# I2C.net
KiCad netlist of a schematic drawn in EAGLE
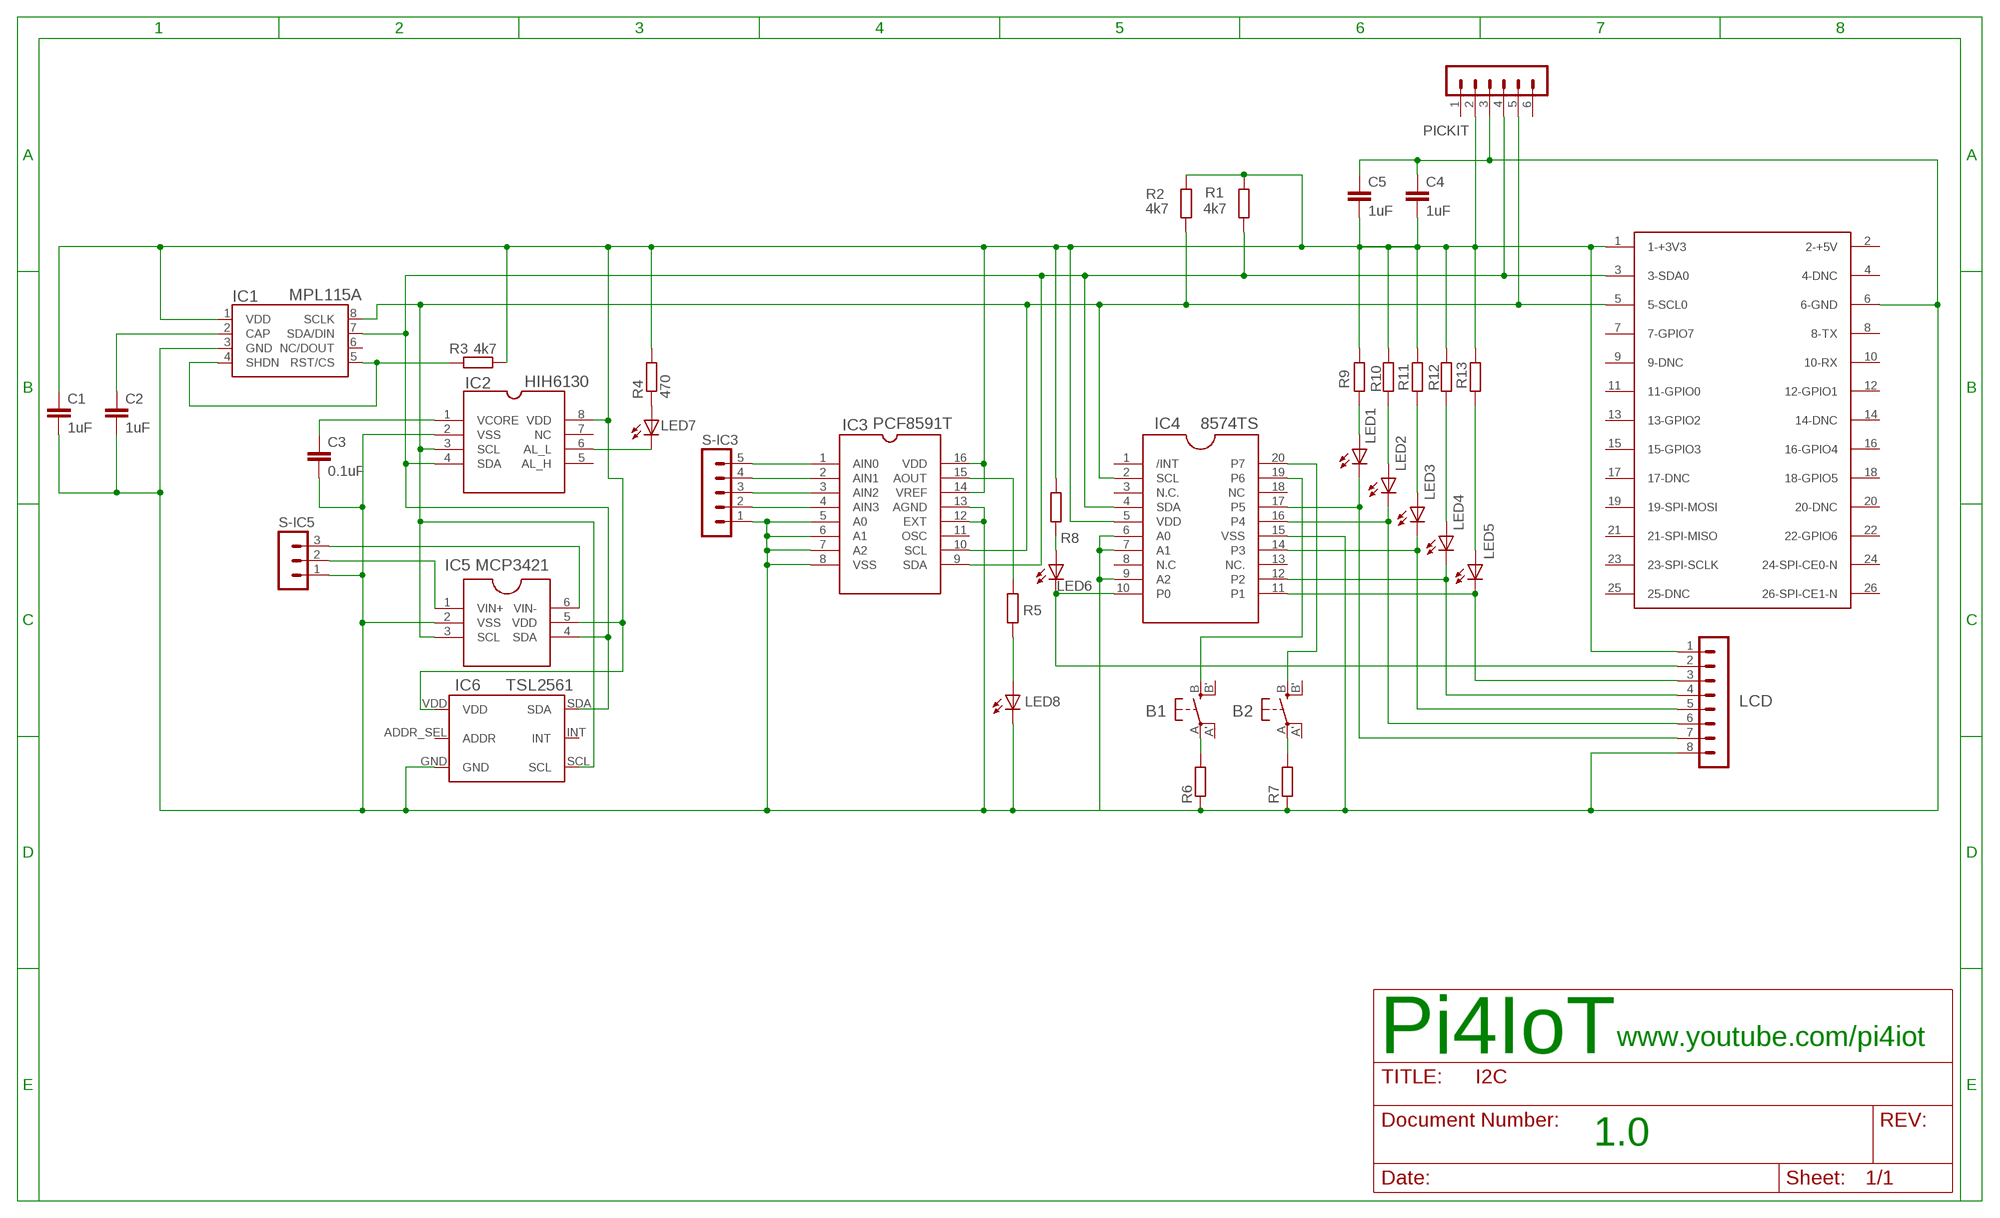
[diagram p0: schematic, sheet 1]

(export (version "E")
  (design (tool "Eeschema 10.0.6"))
  (components
    (comp (ref "B1")
      (value "SWITCH_TACT_SMT")
      (footprint "eagle-import:EVQ-Q2")
      (libsource (lib "eagle-import") (part "SWITCH_TACT_SMT"))
    )
    (comp (ref "B2")
      (value "SWITCH_TACT_SMT")
      (footprint "eagle-import:EVQ-Q2")
      (libsource (lib "eagle-import") (part "SWITCH_TACT_SMT"))
    )
    (comp (ref "C1")
      (value "1uF")
      (footprint "eagle-import:C1206")
      (libsource (lib "eagle-import") (part "C-EUC1206"))
    )
    (comp (ref "C2")
      (value "1uF")
      (footprint "eagle-import:C1206")
      (libsource (lib "eagle-import") (part "C-EUC1206"))
    )
    (comp (ref "C3")
      (value "0.1uF")
      (footprint "eagle-import:C1206")
      (libsource (lib "eagle-import") (part "C-EUC1206"))
    )
    (comp (ref "C4")
      (value "1uF")
      (footprint "eagle-import:C1206")
      (libsource (lib "eagle-import") (part "C-EUC1206"))
    )
    (comp (ref "C5")
      (value "1uF")
      (footprint "eagle-import:C1206")
      (libsource (lib "eagle-import") (part "C-EUC1206"))
    )
    (comp (ref "IC1")
      (value "MPL115A")
      (footprint "eagle-import:LGA8")
      (libsource (lib "eagle-import") (part "MPL115A"))
    )
    (comp (ref "IC2")
      (value "HIH6130")
      (footprint "eagle-import:SO08")
      (libsource (lib "eagle-import") (part "HIH6130"))
    )
    (comp (ref "IC3")
      (value "PCF8591T")
      (footprint "eagle-import:SO-16W")
      (libsource (lib "eagle-import") (part "PCF8591T"))
    )
    (comp (ref "IC4")
      (value "8574TS")
      (footprint "eagle-import:SSOP20")
      (libsource (lib "eagle-import") (part "8574TS"))
    )
    (comp (ref "IC5")
      (value "MCP3421")
      (footprint "eagle-import:SOT23-6")
      (libsource (lib "eagle-import") (part "MCP3421A0T"))
    )
    (comp (ref "IC6")
      (value "TSL2561")
      (footprint "eagle-import:TSL2561T")
      (libsource (lib "eagle-import") (part "TSL2561T"))
    )
    (comp (ref "LCD")
      (value "MA08-1")
      (footprint "eagle-import:MA08-1")
      (libsource (lib "eagle-import") (part "MA08-1"))
    )
    (comp (ref "LED1")
      (value "LEDSML0603")
      (footprint "eagle-import:SML0603")
      (libsource (lib "eagle-import") (part "LEDSML0603"))
    )
    (comp (ref "LED2")
      (value "LEDSML0603")
      (footprint "eagle-import:SML0603")
      (libsource (lib "eagle-import") (part "LEDSML0603"))
    )
    (comp (ref "LED3")
      (value "LEDSML0603")
      (footprint "eagle-import:SML0603")
      (libsource (lib "eagle-import") (part "LEDSML0603"))
    )
    (comp (ref "LED4")
      (value "LEDSML0603")
      (footprint "eagle-import:SML0603")
      (libsource (lib "eagle-import") (part "LEDSML0603"))
    )
    (comp (ref "LED5")
      (value "LEDSML0603")
      (footprint "eagle-import:SML0603")
      (libsource (lib "eagle-import") (part "LEDSML0603"))
    )
    (comp (ref "LED6")
      (value "LEDSML0603")
      (footprint "eagle-import:SML0603")
      (libsource (lib "eagle-import") (part "LEDSML0603"))
    )
    (comp (ref "LED7")
      (value "LEDSML0603")
      (footprint "eagle-import:SML0603")
      (libsource (lib "eagle-import") (part "LEDSML0603"))
    )
    (comp (ref "LED8")
      (value "LEDSML0603")
      (footprint "eagle-import:SML0603")
      (libsource (lib "eagle-import") (part "LEDSML0603"))
    )
    (comp (ref "PI")
      (value "RASPBERRY-PI")
      (footprint "eagle-import:RASPBERRY-PI")
      (libsource (lib "eagle-import") (part "RASPBERRY-PI"))
    )
    (comp (ref "PICKIT")
      (value "MA06-1")
      (footprint "eagle-import:MA06-1")
      (libsource (lib "eagle-import") (part "MA06-1"))
    )
    (comp (ref "R1")
      (value "4k7")
      (footprint "eagle-import:R0603")
      (libsource (lib "eagle-import") (part "R-EU_R0603"))
    )
    (comp (ref "R2")
      (value "4k7")
      (footprint "eagle-import:R0603")
      (libsource (lib "eagle-import") (part "R-EU_R0603"))
    )
    (comp (ref "R3")
      (value "4k7")
      (footprint "eagle-import:R0603")
      (libsource (lib "eagle-import") (part "R-EU_R0603"))
    )
    (comp (ref "R4")
      (value "470")
      (footprint "eagle-import:R0603")
      (libsource (lib "eagle-import") (part "R-EU_R0603"))
    )
    (comp (ref "R5")
      (value "R-EU_R0603")
      (footprint "eagle-import:R0603")
      (libsource (lib "eagle-import") (part "R-EU_R0603"))
    )
    (comp (ref "R6")
      (value "R-EU_R0603")
      (footprint "eagle-import:R0603")
      (libsource (lib "eagle-import") (part "R-EU_R0603"))
    )
    (comp (ref "R7")
      (value "R-EU_R0603")
      (footprint "eagle-import:R0603")
      (libsource (lib "eagle-import") (part "R-EU_R0603"))
    )
    (comp (ref "R8")
      (value "R-EU_R0603")
      (footprint "eagle-import:R0603")
      (libsource (lib "eagle-import") (part "R-EU_R0603"))
    )
    (comp (ref "R9")
      (value "R-EU_R0603")
      (footprint "eagle-import:R0603")
      (libsource (lib "eagle-import") (part "R-EU_R0603"))
    )
    (comp (ref "R10")
      (value "R-EU_R0603")
      (footprint "eagle-import:R0603")
      (libsource (lib "eagle-import") (part "R-EU_R0603"))
    )
    (comp (ref "R11")
      (value "R-EU_R0603")
      (footprint "eagle-import:R0603")
      (libsource (lib "eagle-import") (part "R-EU_R0603"))
    )
    (comp (ref "R12")
      (value "R-EU_R0603")
      (footprint "eagle-import:R0603")
      (libsource (lib "eagle-import") (part "R-EU_R0603"))
    )
    (comp (ref "R13")
      (value "R-EU_R0603")
      (footprint "eagle-import:R0603")
      (libsource (lib "eagle-import") (part "R-EU_R0603"))
    )
    (comp (ref "S-IC3")
      (value "MA05-1")
      (footprint "eagle-import:MA05-1")
      (libsource (lib "eagle-import") (part "MA05-1"))
    )
    (comp (ref "S-IC5")
      (value "MA03-1")
      (footprint "eagle-import:MA03-1")
      (libsource (lib "eagle-import") (part "MA03-1"))
    )
  )
  (nets
    (net (code "1") (name "Net-(B1-P)") (class "Default")
      (node (ref "B1") (pin "A") (pinfunction "P_A") (pintype "passive"))
      (node (ref "R6") (pin "2") (pinfunction "2_2") (pintype "passive"))
    )
    (net (code "2") (name "Net-(B1-S)") (class "Default")
      (node (ref "B1") (pin "B") (pinfunction "S_B") (pintype "passive"))
      (node (ref "IC4") (pin "19") (pinfunction "P6_19") (pintype "bidirectional"))
    )
    (net (code "3") (name "Net-(B2-P)") (class "Default")
      (node (ref "B2") (pin "A") (pinfunction "P_A") (pintype "passive"))
      (node (ref "R7") (pin "2") (pinfunction "2_2") (pintype "passive"))
    )
    (net (code "4") (name "Net-(B2-S)") (class "Default")
      (node (ref "B2") (pin "B") (pinfunction "S_B") (pintype "passive"))
      (node (ref "IC4") (pin "20") (pinfunction "P7_20") (pintype "bidirectional"))
    )
    (net (code "5") (name "Net-(IC1-CAP)") (class "Default")
      (node (ref "C2") (pin "1") (pinfunction "1_1") (pintype "passive"))
      (node (ref "IC1") (pin "2") (pinfunction "CAP_2") (pintype "bidirectional"))
    )
    (net (code "6") (name "Net-(IC1-GND)") (class "Default")
      (node (ref "C1") (pin "2") (pinfunction "2_2") (pintype "passive"))
      (node (ref "C2") (pin "2") (pinfunction "2_2") (pintype "passive"))
      (node (ref "C3") (pin "2") (pinfunction "2_2") (pintype "passive"))
      (node (ref "C4") (pin "1") (pinfunction "1_1") (pintype "passive"))
      (node (ref "C5") (pin "1") (pinfunction "1_1") (pintype "passive"))
      (node (ref "IC1") (pin "3") (pinfunction "GND_3") (pintype "bidirectional"))
      (node (ref "IC2") (pin "2") (pinfunction "VSS_2") (pintype "bidirectional"))
      (node (ref "IC3") (pin "12") (pinfunction "EXT_12") (pintype "bidirectional"))
      (node (ref "IC3") (pin "13") (pinfunction "AGND_13") (pintype "bidirectional"))
      (node (ref "IC3") (pin "5") (pinfunction "A0_5") (pintype "bidirectional"))
      (node (ref "IC3") (pin "6") (pinfunction "A1_6") (pintype "bidirectional"))
      (node (ref "IC3") (pin "7") (pinfunction "A2_7") (pintype "bidirectional"))
      (node (ref "IC3") (pin "8") (pinfunction "VSS_8") (pintype "bidirectional"))
      (node (ref "IC4") (pin "15") (pinfunction "VSS_15") (pintype "bidirectional"))
      (node (ref "IC4") (pin "6") (pinfunction "A0_6") (pintype "bidirectional"))
      (node (ref "IC4") (pin "7") (pinfunction "A1_7") (pintype "bidirectional"))
      (node (ref "IC4") (pin "9") (pinfunction "A2_9") (pintype "bidirectional"))
      (node (ref "IC5") (pin "2") (pinfunction "VSS_2") (pintype "bidirectional"))
      (node (ref "IC6") (pin "GND") (pinfunction "GND_GND") (pintype "passive"))
      (node (ref "LCD") (pin "8") (pinfunction "8_8") (pintype "passive"))
      (node (ref "LED8") (pin "C") (pinfunction "C_C") (pintype "passive"))
      (node (ref "PI") (pin "6") (pinfunction "6-GND_6") (pintype "bidirectional"))
      (node (ref "PICKIT") (pin "3") (pinfunction "3_3") (pintype "passive"))
      (node (ref "R6") (pin "1") (pinfunction "1_1") (pintype "passive"))
      (node (ref "R7") (pin "1") (pinfunction "1_1") (pintype "passive"))
      (node (ref "S-IC3") (pin "1") (pinfunction "1_1") (pintype "passive"))
      (node (ref "S-IC5") (pin "1") (pinfunction "1_1") (pintype "passive"))
    )
    (net (code "7") (name "Net-(IC1-RST{slash}CS)") (class "Default")
      (node (ref "IC1") (pin "4") (pinfunction "SHDN_4") (pintype "bidirectional"))
      (node (ref "IC1") (pin "5") (pinfunction "RST/CS_5") (pintype "bidirectional"))
      (node (ref "R3") (pin "2") (pinfunction "2_2") (pintype "passive"))
    )
    (net (code "8") (name "Net-(IC1-SCLK)") (class "Default")
      (node (ref "IC1") (pin "8") (pinfunction "SCLK_8") (pintype "bidirectional"))
      (node (ref "IC2") (pin "3") (pinfunction "SCL_3") (pintype "bidirectional"))
      (node (ref "IC3") (pin "10") (pinfunction "SCL_10") (pintype "bidirectional"))
      (node (ref "IC4") (pin "2") (pinfunction "SCL_2") (pintype "bidirectional"))
      (node (ref "IC5") (pin "3") (pinfunction "SCL_3") (pintype "bidirectional"))
      (node (ref "IC6") (pin "SCL") (pinfunction "SCL_SCL") (pintype "passive"))
      (node (ref "PI") (pin "5") (pinfunction "5-SCL0_5") (pintype "bidirectional"))
      (node (ref "PICKIT") (pin "5") (pinfunction "5_5") (pintype "passive"))
      (node (ref "R2") (pin "1") (pinfunction "1_1") (pintype "passive"))
    )
    (net (code "9") (name "Net-(IC1-SDA{slash}DIN)") (class "Default")
      (node (ref "IC1") (pin "7") (pinfunction "SDA/DIN_7") (pintype "bidirectional"))
      (node (ref "IC2") (pin "4") (pinfunction "SDA_4") (pintype "bidirectional"))
      (node (ref "IC3") (pin "9") (pinfunction "SDA_9") (pintype "bidirectional"))
      (node (ref "IC4") (pin "4") (pinfunction "SDA_4") (pintype "bidirectional"))
      (node (ref "IC5") (pin "4") (pinfunction "SDA_4") (pintype "bidirectional"))
      (node (ref "IC6") (pin "SDA") (pinfunction "SDA_SDA") (pintype "passive"))
      (node (ref "PI") (pin "3") (pinfunction "3-SDA0_3") (pintype "bidirectional"))
      (node (ref "PICKIT") (pin "4") (pinfunction "4_4") (pintype "passive"))
      (node (ref "R1") (pin "1") (pinfunction "1_1") (pintype "passive"))
    )
    (net (code "10") (name "Net-(IC1-VDD)") (class "Default")
      (node (ref "C1") (pin "1") (pinfunction "1_1") (pintype "passive"))
      (node (ref "C4") (pin "2") (pinfunction "2_2") (pintype "passive"))
      (node (ref "C5") (pin "2") (pinfunction "2_2") (pintype "passive"))
      (node (ref "IC1") (pin "1") (pinfunction "VDD_1") (pintype "bidirectional"))
      (node (ref "IC2") (pin "8") (pinfunction "VDD_8") (pintype "bidirectional"))
      (node (ref "IC3") (pin "14") (pinfunction "VREF_14") (pintype "bidirectional"))
      (node (ref "IC3") (pin "16") (pinfunction "VDD_16") (pintype "bidirectional"))
      (node (ref "IC4") (pin "5") (pinfunction "VDD_5") (pintype "bidirectional"))
      (node (ref "IC5") (pin "5") (pinfunction "VDD_5") (pintype "bidirectional"))
      (node (ref "IC6") (pin "VDD") (pinfunction "VDD_VDD") (pintype "passive"))
      (node (ref "LCD") (pin "1") (pinfunction "1_1") (pintype "passive"))
      (node (ref "PI") (pin "1") (pinfunction "1-+3V3_1") (pintype "bidirectional"))
      (node (ref "PICKIT") (pin "2") (pinfunction "2_2") (pintype "passive"))
      (node (ref "R1") (pin "2") (pinfunction "2_2") (pintype "passive"))
      (node (ref "R10") (pin "2") (pinfunction "2_2") (pintype "passive"))
      (node (ref "R11") (pin "2") (pinfunction "2_2") (pintype "passive"))
      (node (ref "R12") (pin "2") (pinfunction "2_2") (pintype "passive"))
      (node (ref "R13") (pin "2") (pinfunction "2_2") (pintype "passive"))
      (node (ref "R2") (pin "2") (pinfunction "2_2") (pintype "passive"))
      (node (ref "R3") (pin "1") (pinfunction "1_1") (pintype "passive"))
      (node (ref "R4") (pin "2") (pinfunction "2_2") (pintype "passive"))
      (node (ref "R8") (pin "2") (pinfunction "2_2") (pintype "passive"))
      (node (ref "R9") (pin "2") (pinfunction "2_2") (pintype "passive"))
    )
    (net (code "11") (name "Net-(IC2-AL_L)") (class "Default")
      (node (ref "IC2") (pin "6") (pinfunction "AL_L_6") (pintype "bidirectional"))
      (node (ref "LED7") (pin "C") (pinfunction "C_C") (pintype "passive"))
    )
    (net (code "12") (name "Net-(IC2-VCORE)") (class "Default")
      (node (ref "C3") (pin "1") (pinfunction "1_1") (pintype "passive"))
      (node (ref "IC2") (pin "1") (pinfunction "VCORE_1") (pintype "bidirectional"))
    )
    (net (code "13") (name "Net-(IC3-AIN0)") (class "Default")
      (node (ref "IC3") (pin "1") (pinfunction "AIN0_1") (pintype "bidirectional"))
      (node (ref "S-IC3") (pin "5") (pinfunction "5_5") (pintype "passive"))
    )
    (net (code "14") (name "Net-(IC3-AIN1)") (class "Default")
      (node (ref "IC3") (pin "2") (pinfunction "AIN1_2") (pintype "bidirectional"))
      (node (ref "S-IC3") (pin "4") (pinfunction "4_4") (pintype "passive"))
    )
    (net (code "15") (name "Net-(IC3-AIN2)") (class "Default")
      (node (ref "IC3") (pin "3") (pinfunction "AIN2_3") (pintype "bidirectional"))
      (node (ref "S-IC3") (pin "3") (pinfunction "3_3") (pintype "passive"))
    )
    (net (code "16") (name "Net-(IC3-AIN3)") (class "Default")
      (node (ref "IC3") (pin "4") (pinfunction "AIN3_4") (pintype "bidirectional"))
      (node (ref "S-IC3") (pin "2") (pinfunction "2_2") (pintype "passive"))
    )
    (net (code "17") (name "Net-(IC3-AOUT)") (class "Default")
      (node (ref "IC3") (pin "15") (pinfunction "AOUT_15") (pintype "bidirectional"))
      (node (ref "R5") (pin "2") (pinfunction "2_2") (pintype "passive"))
    )
    (net (code "18") (name "Net-(IC4-P0)") (class "Default")
      (node (ref "IC4") (pin "10") (pinfunction "P0_10") (pintype "bidirectional"))
      (node (ref "LCD") (pin "2") (pinfunction "2_2") (pintype "passive"))
      (node (ref "LED6") (pin "C") (pinfunction "C_C") (pintype "passive"))
    )
    (net (code "19") (name "Net-(IC4-P1)") (class "Default")
      (node (ref "IC4") (pin "11") (pinfunction "P1_11") (pintype "bidirectional"))
      (node (ref "LCD") (pin "3") (pinfunction "3_3") (pintype "passive"))
      (node (ref "LED5") (pin "C") (pinfunction "C_C") (pintype "passive"))
    )
    (net (code "20") (name "Net-(IC4-P2)") (class "Default")
      (node (ref "IC4") (pin "12") (pinfunction "P2_12") (pintype "bidirectional"))
      (node (ref "LCD") (pin "4") (pinfunction "4_4") (pintype "passive"))
      (node (ref "LED4") (pin "C") (pinfunction "C_C") (pintype "passive"))
    )
    (net (code "21") (name "Net-(IC4-P3)") (class "Default")
      (node (ref "IC4") (pin "14") (pinfunction "P3_14") (pintype "bidirectional"))
      (node (ref "LCD") (pin "5") (pinfunction "5_5") (pintype "passive"))
      (node (ref "LED3") (pin "C") (pinfunction "C_C") (pintype "passive"))
    )
    (net (code "22") (name "Net-(IC4-P4)") (class "Default")
      (node (ref "IC4") (pin "16") (pinfunction "P4_16") (pintype "bidirectional"))
      (node (ref "LCD") (pin "6") (pinfunction "6_6") (pintype "passive"))
      (node (ref "LED2") (pin "C") (pinfunction "C_C") (pintype "passive"))
    )
    (net (code "23") (name "Net-(IC4-P5)") (class "Default")
      (node (ref "IC4") (pin "17") (pinfunction "P5_17") (pintype "bidirectional"))
      (node (ref "LCD") (pin "7") (pinfunction "7_7") (pintype "passive"))
      (node (ref "LED1") (pin "C") (pinfunction "C_C") (pintype "passive"))
    )
    (net (code "24") (name "Net-(IC5-VIN+)") (class "Default")
      (node (ref "IC5") (pin "1") (pinfunction "VIN+_1") (pintype "bidirectional"))
      (node (ref "S-IC5") (pin "2") (pinfunction "2_2") (pintype "passive"))
    )
    (net (code "25") (name "Net-(IC5-VIN-)") (class "Default")
      (node (ref "IC5") (pin "6") (pinfunction "VIN-_6") (pintype "bidirectional"))
      (node (ref "S-IC5") (pin "3") (pinfunction "3_3") (pintype "passive"))
    )
    (net (code "26") (name "Net-(LED1-PadA)") (class "Default")
      (node (ref "LED1") (pin "A") (pinfunction "A_A") (pintype "passive"))
      (node (ref "R9") (pin "1") (pinfunction "1_1") (pintype "passive"))
    )
    (net (code "27") (name "Net-(LED2-PadA)") (class "Default")
      (node (ref "LED2") (pin "A") (pinfunction "A_A") (pintype "passive"))
      (node (ref "R10") (pin "1") (pinfunction "1_1") (pintype "passive"))
    )
    (net (code "28") (name "Net-(LED3-PadA)") (class "Default")
      (node (ref "LED3") (pin "A") (pinfunction "A_A") (pintype "passive"))
      (node (ref "R11") (pin "1") (pinfunction "1_1") (pintype "passive"))
    )
    (net (code "29") (name "Net-(LED4-PadA)") (class "Default")
      (node (ref "LED4") (pin "A") (pinfunction "A_A") (pintype "passive"))
      (node (ref "R12") (pin "1") (pinfunction "1_1") (pintype "passive"))
    )
    (net (code "30") (name "Net-(LED5-PadA)") (class "Default")
      (node (ref "LED5") (pin "A") (pinfunction "A_A") (pintype "passive"))
      (node (ref "R13") (pin "1") (pinfunction "1_1") (pintype "passive"))
    )
    (net (code "31") (name "Net-(LED6-PadA)") (class "Default")
      (node (ref "LED6") (pin "A") (pinfunction "A_A") (pintype "passive"))
      (node (ref "R8") (pin "1") (pinfunction "1_1") (pintype "passive"))
    )
    (net (code "32") (name "Net-(LED7-PadA)") (class "Default")
      (node (ref "LED7") (pin "A") (pinfunction "A_A") (pintype "passive"))
      (node (ref "R4") (pin "1") (pinfunction "1_1") (pintype "passive"))
    )
    (net (code "33") (name "Net-(LED8-PadA)") (class "Default")
      (node (ref "LED8") (pin "A") (pinfunction "A_A") (pintype "passive"))
      (node (ref "R5") (pin "1") (pinfunction "1_1") (pintype "passive"))
    )
    (net (code "34") (name "unconnected-(B1-P1-PadA')") (class "Default")
      (node (ref "B1") (pin "A'") (pinfunction "P1_A'") (pintype "passive"))
    )
    (net (code "35") (name "unconnected-(B1-S1-PadB')") (class "Default")
      (node (ref "B1") (pin "B'") (pinfunction "S1_B'") (pintype "passive"))
    )
    (net (code "36") (name "unconnected-(B2-P1-PadA')") (class "Default")
      (node (ref "B2") (pin "A'") (pinfunction "P1_A'") (pintype "passive"))
    )
    (net (code "37") (name "unconnected-(B2-S1-PadB')") (class "Default")
      (node (ref "B2") (pin "B'") (pinfunction "S1_B'") (pintype "passive"))
    )
    (net (code "38") (name "unconnected-(IC1-NC{slash}DOUT-Pad6)") (class "Default")
      (node (ref "IC1") (pin "6") (pinfunction "NC/DOUT_6") (pintype "bidirectional"))
    )
    (net (code "39") (name "unconnected-(IC2-AL_H-Pad5)") (class "Default")
      (node (ref "IC2") (pin "5") (pinfunction "AL_H_5") (pintype "bidirectional"))
    )
    (net (code "40") (name "unconnected-(IC2-NC-Pad7)") (class "Default")
      (node (ref "IC2") (pin "7") (pinfunction "NC_7") (pintype "bidirectional"))
    )
    (net (code "41") (name "unconnected-(IC3-OSC-Pad11)") (class "Default")
      (node (ref "IC3") (pin "11") (pinfunction "OSC_11") (pintype "bidirectional"))
    )
    (net (code "42") (name "unconnected-(IC4-N.C-Pad8)") (class "Default")
      (node (ref "IC4") (pin "8") (pinfunction "N.C_8") (pintype "bidirectional"))
    )
    (net (code "43") (name "unconnected-(IC4-N.C.-Pad3)") (class "Default")
      (node (ref "IC4") (pin "3") (pinfunction "N.C._3") (pintype "bidirectional"))
    )
    (net (code "44") (name "unconnected-(IC4-NC-Pad18)") (class "Default")
      (node (ref "IC4") (pin "18") (pinfunction "NC_18") (pintype "bidirectional"))
    )
    (net (code "45") (name "unconnected-(IC4-NC.-Pad13)") (class "Default")
      (node (ref "IC4") (pin "13") (pinfunction "NC._13") (pintype "bidirectional"))
    )
    (net (code "46") (name "unconnected-(IC4-{slash}INT-Pad1)") (class "Default")
      (node (ref "IC4") (pin "1") (pinfunction "/INT_1") (pintype "bidirectional"))
    )
    (net (code "47") (name "unconnected-(IC6-ADDR-PadADDR_SEL)") (class "Default")
      (node (ref "IC6") (pin "ADDR_SEL") (pinfunction "ADDR_ADDR_SEL") (pintype "passive"))
    )
    (net (code "48") (name "unconnected-(IC6-PadINT)") (class "Default")
      (node (ref "IC6") (pin "INT") (pinfunction "INT_INT") (pintype "passive"))
    )
    (net (code "49") (name "unconnected-(PI-2-+5V-Pad2)") (class "Default")
      (node (ref "PI") (pin "2") (pinfunction "2-+5V_2") (pintype "bidirectional"))
    )
    (net (code "50") (name "unconnected-(PI-4-DNC-Pad4)") (class "Default")
      (node (ref "PI") (pin "4") (pinfunction "4-DNC_4") (pintype "bidirectional"))
    )
    (net (code "51") (name "unconnected-(PI-7-GPIO7-Pad7)") (class "Default")
      (node (ref "PI") (pin "7") (pinfunction "7-GPIO7_7") (pintype "bidirectional"))
    )
    (net (code "52") (name "unconnected-(PI-8-TX-Pad8)") (class "Default")
      (node (ref "PI") (pin "8") (pinfunction "8-TX_8") (pintype "bidirectional"))
    )
    (net (code "53") (name "unconnected-(PI-9-DNC-Pad9)") (class "Default")
      (node (ref "PI") (pin "9") (pinfunction "9-DNC_9") (pintype "bidirectional"))
    )
    (net (code "54") (name "unconnected-(PI-10-RX-Pad10)") (class "Default")
      (node (ref "PI") (pin "10") (pinfunction "10-RX_10") (pintype "bidirectional"))
    )
    (net (code "55") (name "unconnected-(PI-11-GPIO0-Pad11)") (class "Default")
      (node (ref "PI") (pin "11") (pinfunction "11-GPIO0_11") (pintype "bidirectional"))
    )
    (net (code "56") (name "unconnected-(PI-12-GPIO1-Pad12)") (class "Default")
      (node (ref "PI") (pin "12") (pinfunction "12-GPIO1_12") (pintype "bidirectional"))
    )
    (net (code "57") (name "unconnected-(PI-13-GPIO2-Pad13)") (class "Default")
      (node (ref "PI") (pin "13") (pinfunction "13-GPIO2_13") (pintype "bidirectional"))
    )
    (net (code "58") (name "unconnected-(PI-14-DNC-Pad14)") (class "Default")
      (node (ref "PI") (pin "14") (pinfunction "14-DNC_14") (pintype "bidirectional"))
    )
    (net (code "59") (name "unconnected-(PI-15-GPIO3-Pad15)") (class "Default")
      (node (ref "PI") (pin "15") (pinfunction "15-GPIO3_15") (pintype "bidirectional"))
    )
    (net (code "60") (name "unconnected-(PI-16-GPIO4-Pad16)") (class "Default")
      (node (ref "PI") (pin "16") (pinfunction "16-GPIO4_16") (pintype "bidirectional"))
    )
    (net (code "61") (name "unconnected-(PI-17-DNC-Pad17)") (class "Default")
      (node (ref "PI") (pin "17") (pinfunction "17-DNC_17") (pintype "bidirectional"))
    )
    (net (code "62") (name "unconnected-(PI-18-GPIO5-Pad18)") (class "Default")
      (node (ref "PI") (pin "18") (pinfunction "18-GPIO5_18") (pintype "bidirectional"))
    )
    (net (code "63") (name "unconnected-(PI-19-SPI-MOSI-Pad19)") (class "Default")
      (node (ref "PI") (pin "19") (pinfunction "19-SPI-MOSI_19") (pintype "bidirectional"))
    )
    (net (code "64") (name "unconnected-(PI-20-DNC-Pad20)") (class "Default")
      (node (ref "PI") (pin "20") (pinfunction "20-DNC_20") (pintype "bidirectional"))
    )
    (net (code "65") (name "unconnected-(PI-21-SPI-MISO-Pad21)") (class "Default")
      (node (ref "PI") (pin "21") (pinfunction "21-SPI-MISO_21") (pintype "bidirectional"))
    )
    (net (code "66") (name "unconnected-(PI-22-GPIO6-Pad22)") (class "Default")
      (node (ref "PI") (pin "22") (pinfunction "22-GPIO6_22") (pintype "bidirectional"))
    )
    (net (code "67") (name "unconnected-(PI-23-SPI-SCLK-Pad23)") (class "Default")
      (node (ref "PI") (pin "23") (pinfunction "23-SPI-SCLK_23") (pintype "bidirectional"))
    )
    (net (code "68") (name "unconnected-(PI-24-SPI-CE0-N-Pad24)") (class "Default")
      (node (ref "PI") (pin "24") (pinfunction "24-SPI-CE0-N_24") (pintype "bidirectional"))
    )
    (net (code "69") (name "unconnected-(PI-25-DNC-Pad25)") (class "Default")
      (node (ref "PI") (pin "25") (pinfunction "25-DNC_25") (pintype "bidirectional"))
    )
    (net (code "70") (name "unconnected-(PI-26-SPI-CE1-N-Pad26)") (class "Default")
      (node (ref "PI") (pin "26") (pinfunction "26-SPI-CE1-N_26") (pintype "bidirectional"))
    )
    (net (code "71") (name "unconnected-(PICKIT-Pad1)") (class "Default")
      (node (ref "PICKIT") (pin "1") (pinfunction "1_1") (pintype "passive"))
    )
    (net (code "72") (name "unconnected-(PICKIT-Pad6)") (class "Default")
      (node (ref "PICKIT") (pin "6") (pinfunction "6_6") (pintype "passive"))
    )
  )
)
